# Arduino_Shield_Connection.net
KiCad netlist of a schematic drawn in Altium Designer
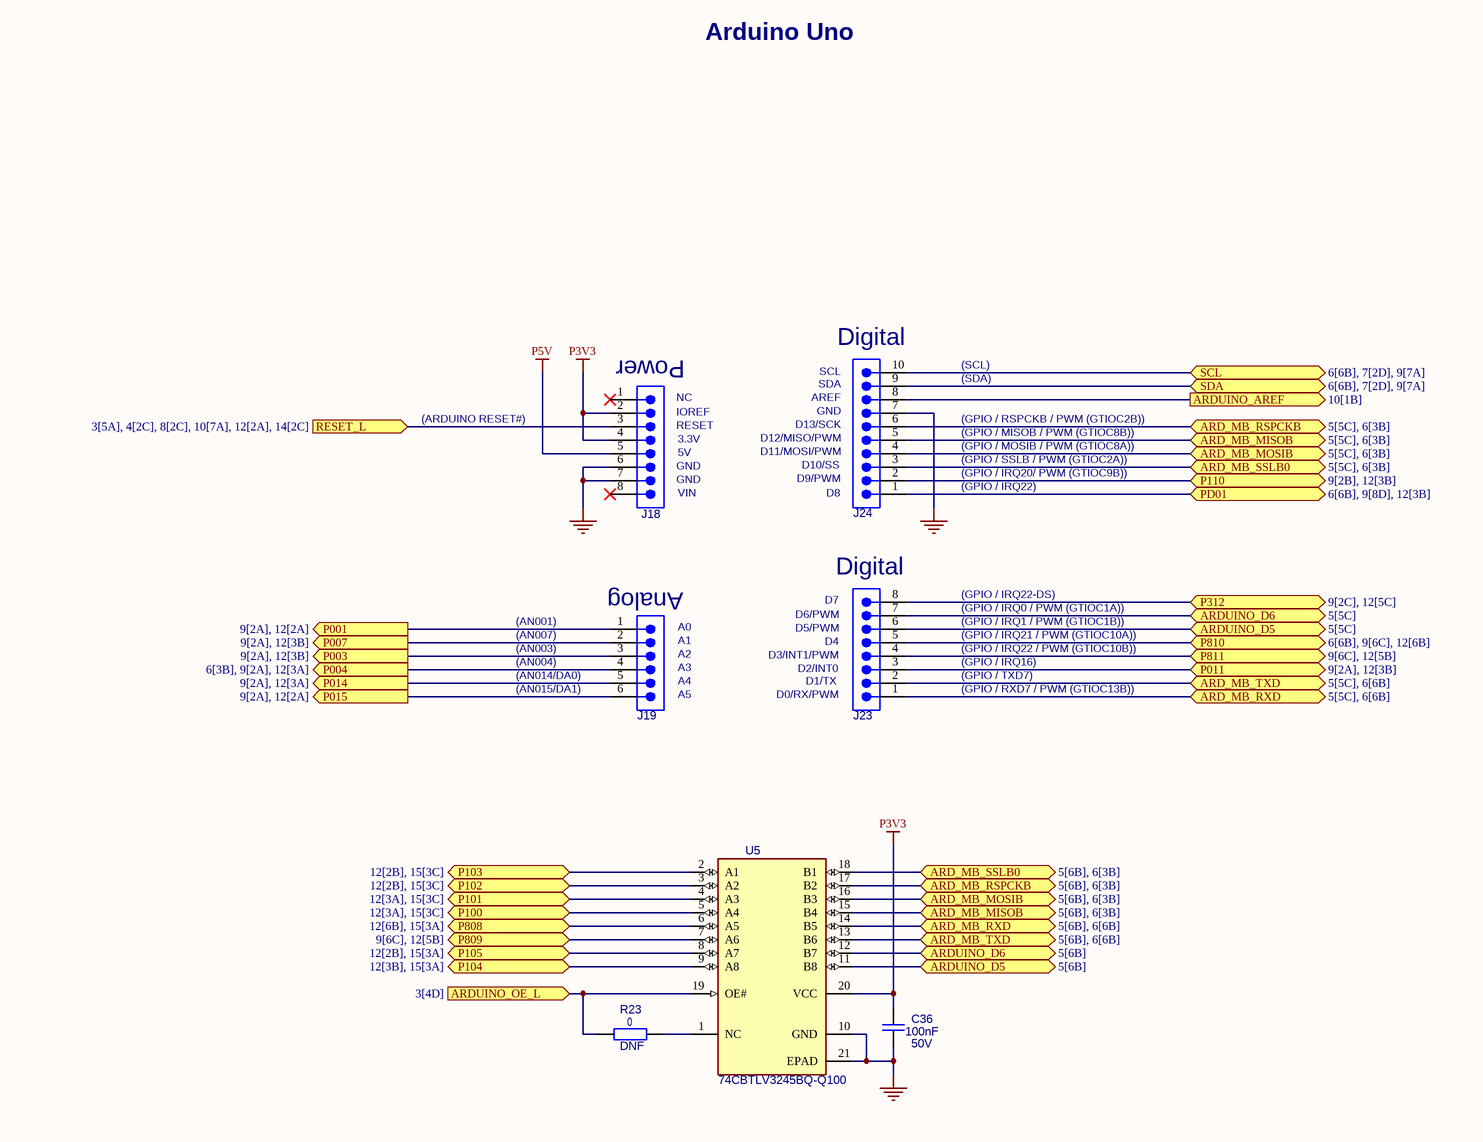
[diagram p0: Arduino Shield Connection.SchDoc]

(export (version "E")
  (design (tool "Eeschema 10.0.6"))
  (components
    (comp (ref "C36")
      (value "100nF")
      (footprint "C_EIA0402_0p55")
      (description "Capacitor,EIA0402,100n,50V,X7R")
      (fields
        (field (name "TOLERANCE") "10%")
        (field (name "OPERATING VOLTAGE MAX") "50V")
        (field (name "Comment") "Capacitor")
      )
      (libsource (lib "ek-ra8d2_mp - Customer") (part "Capacitor"))
    )
    (comp (ref "J18")
      (value "NPTC081KFXC-RC")
      (footprint "sul_NPTC081KFXC-RC")
      (description "Header, 8way, 1 Row, Vertical, 2.54mm, SMD")
      (libsource (lib "ek-ra8d2_mp - Customer") (part "CON_008"))
    )
    (comp (ref "J19")
      (value "NPTC061KFXC-RC")
      (footprint "sul_NPTC061KFXC-RC")
      (description "Header, 6way, 1 Row, Vertical, 2.54mm, SMD")
      (libsource (lib "ek-ra8d2_mp - Customer") (part "CON_006"))
    )
    (comp (ref "J23")
      (value "NPTC081KFXC-RC")
      (footprint "sul_NPTC081KFXC-RC")
      (description "Header, 8way, 1 Row, Vertical, 2.54mm, SMD")
      (libsource (lib "") (part "CON_008_1"))
    )
    (comp (ref "J24")
      (value "NPTC101KFXC-RC")
      (footprint "sul_NPTC101KFXC-RC")
      (description "Header, 10way, 1 Row, Vertical, 2.54mm, SMD")
      (libsource (lib "ek-ra8d2_mp - Customer") (part "CON_010"))
    )
    (comp (ref "R23")
      (value "0")
      (footprint "R_EIA0402")
      (description "Resistor,EIA0402,0,0.0625W")
      (fields (field (name "POWER") "62.5mW") (field (name "TOLERANCE") "5%") (field (name "DNF") "DNF"))
      (libsource (lib "ek-ra8d2_mp - Customer") (part "Resistor"))
    )
    (comp (ref "U5")
      (value "74CBTLV3245BQ-Q100")
      (footprint "nex_SOT-764-1_DHVQFN20")
      (description "Octal FET Bus Switch, 5 ohm, 0.3ns max delay, DHVQFN20")
      (libsource (lib "ek-ra8d2_mp - Customer") (part "nex_74CBTLV3245-Q100"))
    )
  )
  (nets
    (net (code "1") (name "/ARDUINO_AREF") (class "Default")
      (node (ref "J24") (pin "8") (pinfunction "8_8") (pintype "passive"))
    )
    (net (code "2") (name "/ARDUINO_D5") (class "Default")
      (node (ref "J23") (pin "6") (pinfunction "6_6") (pintype "passive"))
      (node (ref "U5") (pin "11") (pinfunction "B8_11") (pintype "bidirectional"))
    )
    (net (code "3") (name "/ARDUINO_D6") (class "Default")
      (node (ref "J23") (pin "7") (pinfunction "7_7") (pintype "passive"))
      (node (ref "U5") (pin "12") (pinfunction "B7_12") (pintype "bidirectional"))
    )
    (net (code "4") (name "/ARDUINO_OE_L") (class "Default")
      (node (ref "R23") (pin "1") (pinfunction "1_1") (pintype "passive"))
      (node (ref "U5") (pin "19") (pinfunction "OE#_19") (pintype "input"))
    )
    (net (code "5") (name "/ARD_MB_MISOB") (class "Default")
      (node (ref "J24") (pin "5") (pinfunction "5_5") (pintype "passive"))
      (node (ref "U5") (pin "15") (pinfunction "B4_15") (pintype "bidirectional"))
    )
    (net (code "6") (name "/ARD_MB_MOSIB") (class "Default")
      (node (ref "J24") (pin "4") (pinfunction "4_4") (pintype "passive"))
      (node (ref "U5") (pin "16") (pinfunction "B3_16") (pintype "bidirectional"))
    )
    (net (code "7") (name "/ARD_MB_RSPCKB") (class "Default")
      (node (ref "J24") (pin "6") (pinfunction "6_6") (pintype "passive"))
      (node (ref "U5") (pin "17") (pinfunction "B2_17") (pintype "bidirectional"))
    )
    (net (code "8") (name "/ARD_MB_RXD") (class "Default")
      (node (ref "J23") (pin "1") (pinfunction "1_1") (pintype "passive"))
      (node (ref "U5") (pin "14") (pinfunction "B5_14") (pintype "bidirectional"))
    )
    (net (code "9") (name "/ARD_MB_SSLB0") (class "Default")
      (node (ref "J24") (pin "3") (pinfunction "3_3") (pintype "passive"))
      (node (ref "U5") (pin "18") (pinfunction "B1_18") (pintype "bidirectional"))
    )
    (net (code "10") (name "/ARD_MB_TXD") (class "Default")
      (node (ref "J23") (pin "2") (pinfunction "2_2") (pintype "passive"))
      (node (ref "U5") (pin "13") (pinfunction "B6_13") (pintype "bidirectional"))
    )
    (net (code "11") (name "/P001") (class "Default")
      (node (ref "J19") (pin "1") (pinfunction "1_1") (pintype "passive"))
    )
    (net (code "12") (name "/P003") (class "Default")
      (node (ref "J19") (pin "3") (pinfunction "3_3") (pintype "passive"))
    )
    (net (code "13") (name "/P004") (class "Default")
      (node (ref "J19") (pin "4") (pinfunction "4_4") (pintype "passive"))
    )
    (net (code "14") (name "/P007") (class "Default")
      (node (ref "J19") (pin "2") (pinfunction "2_2") (pintype "passive"))
    )
    (net (code "15") (name "/P011") (class "Default")
      (node (ref "J23") (pin "3") (pinfunction "3_3") (pintype "passive"))
    )
    (net (code "16") (name "/P014") (class "Default")
      (node (ref "J19") (pin "5") (pinfunction "5_5") (pintype "passive"))
    )
    (net (code "17") (name "/P015") (class "Default")
      (node (ref "J19") (pin "6") (pinfunction "6_6") (pintype "passive"))
    )
    (net (code "18") (name "/P100") (class "Default")
      (node (ref "U5") (pin "5") (pinfunction "A4_5") (pintype "bidirectional"))
    )
    (net (code "19") (name "/P101") (class "Default")
      (node (ref "U5") (pin "4") (pinfunction "A3_4") (pintype "bidirectional"))
    )
    (net (code "20") (name "/P102") (class "Default")
      (node (ref "U5") (pin "3") (pinfunction "A2_3") (pintype "bidirectional"))
    )
    (net (code "21") (name "/P103") (class "Default")
      (node (ref "U5") (pin "2") (pinfunction "A1_2") (pintype "bidirectional"))
    )
    (net (code "22") (name "/P104") (class "Default")
      (node (ref "U5") (pin "9") (pinfunction "A8_9") (pintype "bidirectional"))
    )
    (net (code "23") (name "/P105") (class "Default")
      (node (ref "U5") (pin "8") (pinfunction "A7_8") (pintype "bidirectional"))
    )
    (net (code "24") (name "/P110") (class "Default")
      (node (ref "J24") (pin "2") (pinfunction "2_2") (pintype "passive"))
    )
    (net (code "25") (name "/P312") (class "Default")
      (node (ref "J23") (pin "8") (pinfunction "8_8") (pintype "passive"))
    )
    (net (code "26") (name "/P808") (class "Default")
      (node (ref "U5") (pin "6") (pinfunction "A5_6") (pintype "bidirectional"))
    )
    (net (code "27") (name "/P809") (class "Default")
      (node (ref "U5") (pin "7") (pinfunction "A6_7") (pintype "bidirectional"))
    )
    (net (code "28") (name "/P810") (class "Default")
      (node (ref "J23") (pin "5") (pinfunction "5_5") (pintype "passive"))
    )
    (net (code "29") (name "/P811") (class "Default")
      (node (ref "J23") (pin "4") (pinfunction "4_4") (pintype "passive"))
    )
    (net (code "30") (name "/PD01") (class "Default")
      (node (ref "J24") (pin "1") (pinfunction "1_1") (pintype "passive"))
    )
    (net (code "31") (name "/RESET_L") (class "Default")
      (node (ref "J18") (pin "3") (pinfunction "3_3") (pintype "passive"))
    )
    (net (code "32") (name "/SCL") (class "Default")
      (node (ref "J24") (pin "10") (pinfunction "10_10") (pintype "passive"))
    )
    (net (code "33") (name "/SDA") (class "Default")
      (node (ref "J24") (pin "9") (pinfunction "9_9") (pintype "passive"))
    )
    (net (code "34") (name "GND") (class "Default")
      (node (ref "C36") (pin "1") (pinfunction "1_1") (pintype "passive"))
      (node (ref "J18") (pin "6") (pinfunction "6_6") (pintype "passive"))
      (node (ref "J18") (pin "7") (pinfunction "7_7") (pintype "passive"))
      (node (ref "J24") (pin "7") (pinfunction "7_7") (pintype "passive"))
      (node (ref "U5") (pin "10") (pinfunction "GND_10") (pintype "power_in"))
      (node (ref "U5") (pin "21") (pinfunction "EPAD_21") (pintype "power_in"))
    )
    (net (code "35") (name "Net-(U5-NC)") (class "Default")
      (node (ref "R23") (pin "2") (pinfunction "2_2") (pintype "passive"))
      (node (ref "U5") (pin "1") (pinfunction "NC_1") (pintype "passive"))
    )
    (net (code "36") (name "P3V3") (class "Default")
      (node (ref "C36") (pin "2") (pinfunction "2_2") (pintype "passive"))
      (node (ref "J18") (pin "2") (pinfunction "2_2") (pintype "passive"))
      (node (ref "J18") (pin "4") (pinfunction "4_4") (pintype "passive"))
      (node (ref "U5") (pin "20") (pinfunction "VCC_20") (pintype "power_in"))
    )
    (net (code "37") (name "P5V") (class "Default")
      (node (ref "J18") (pin "5") (pinfunction "5_5") (pintype "passive"))
    )
    (net (code "38") (name "unconnected-(J18-Pad1)") (class "Default")
      (node (ref "J18") (pin "1") (pinfunction "1_1") (pintype "passive+no_connect"))
    )
    (net (code "39") (name "unconnected-(J18-Pad8)") (class "Default")
      (node (ref "J18") (pin "8") (pinfunction "8_8") (pintype "passive+no_connect"))
    )
  )
)
